# M707A.net
KiCad netlist of a schematic drawn in EAGLE
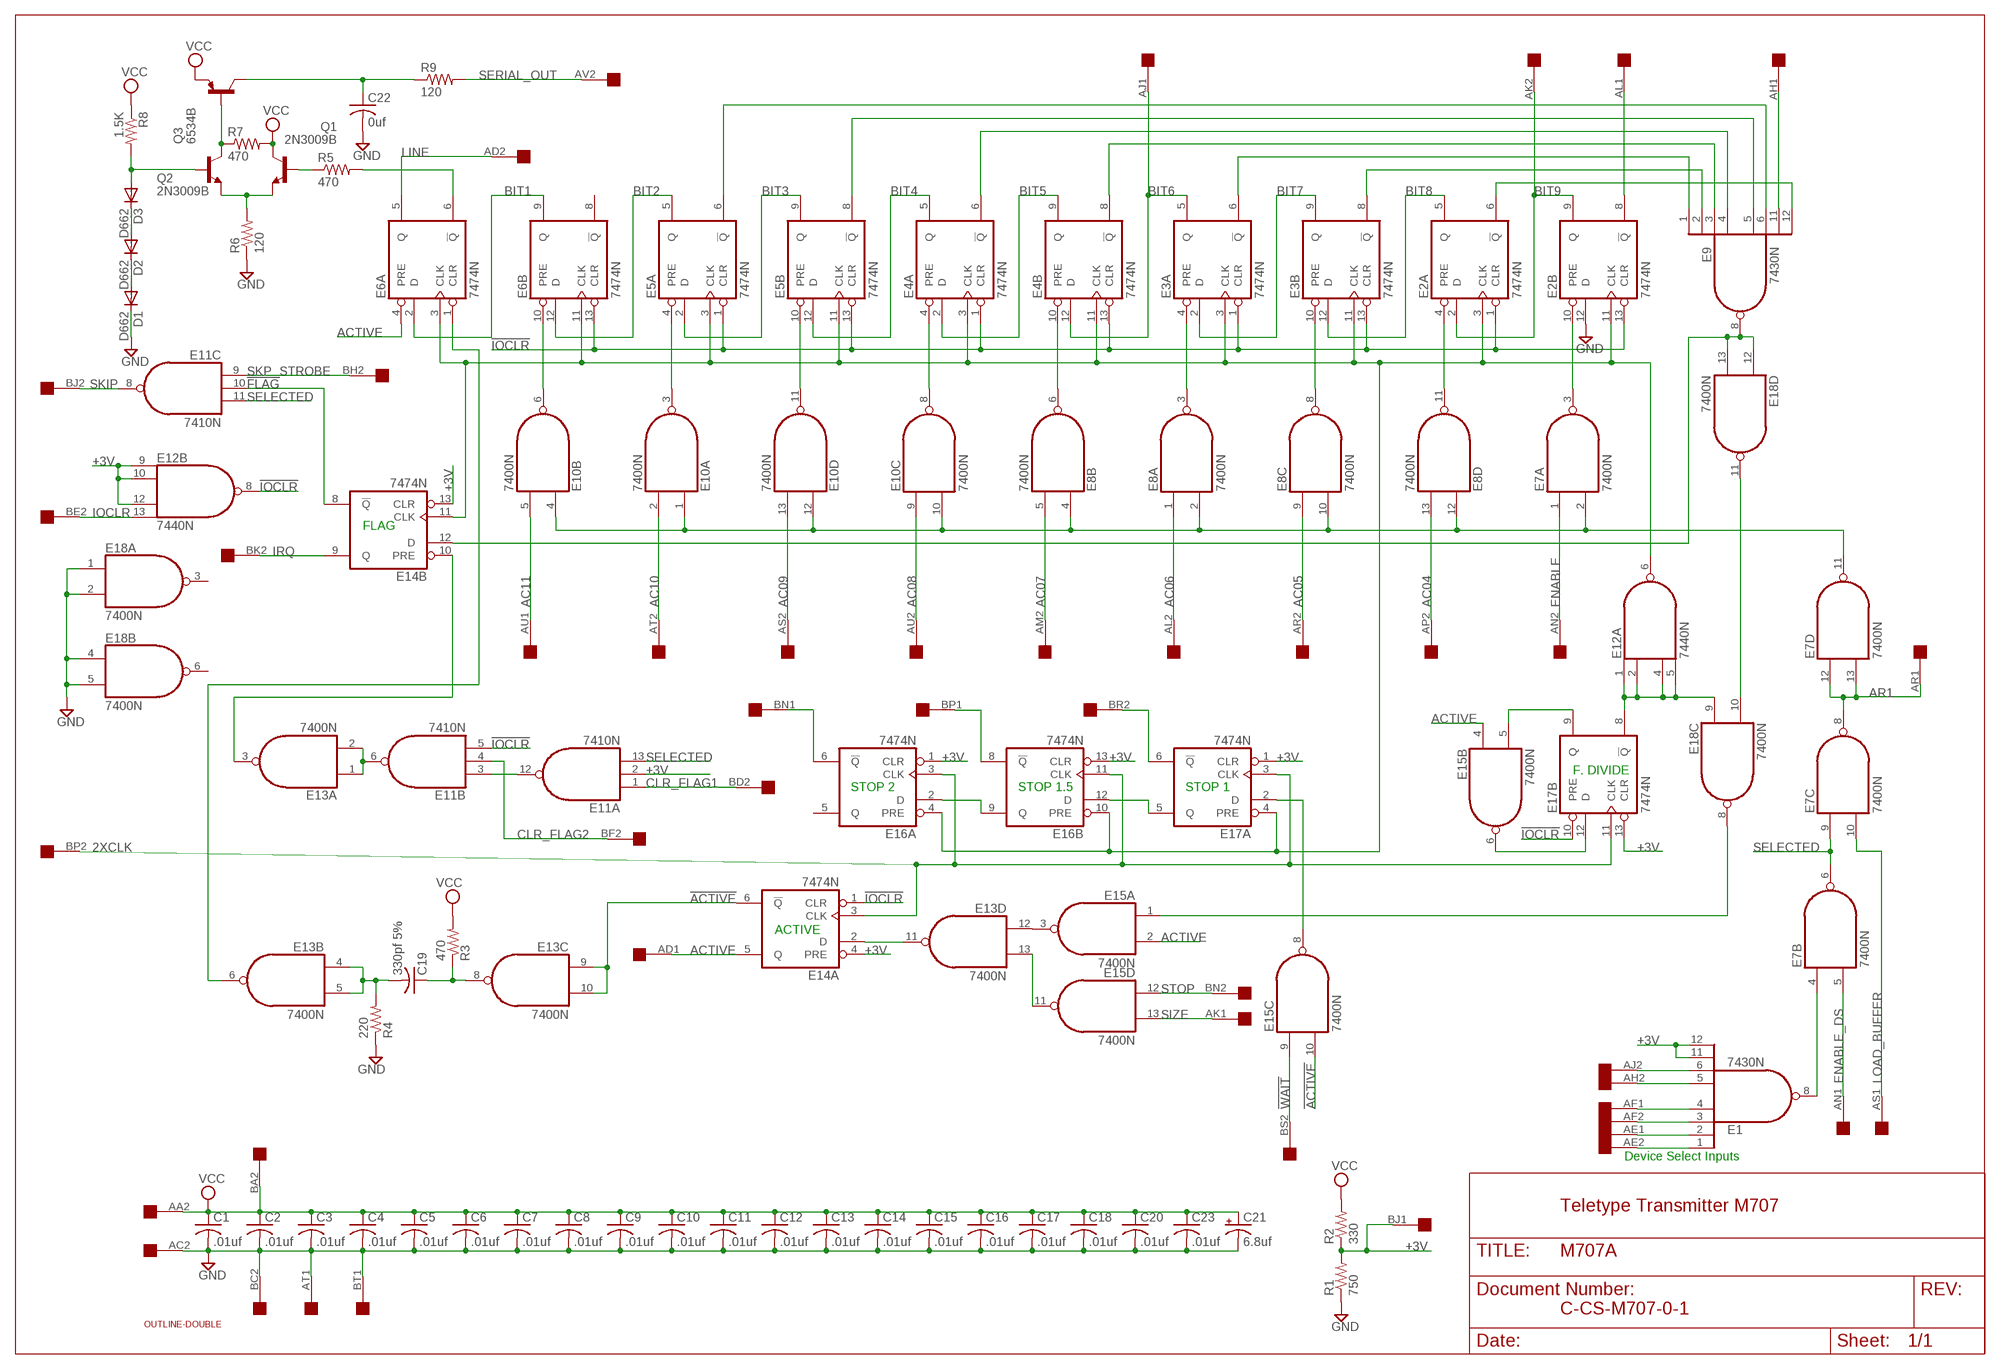
[diagram p0: schematic, sheet 1]

(export (version "E")
  (design (tool "Eeschema 10.0.6"))
  (components
    (comp (ref "C1")
      (value ".01uf")
      (footprint "eagle-import:C075-032X103")
      (libsource (lib "eagle-import") (part "C-US075-032X103"))
    )
    (comp (ref "C2")
      (value ".01uf")
      (footprint "eagle-import:C075-032X103")
      (libsource (lib "eagle-import") (part "C-US075-032X103"))
    )
    (comp (ref "C3")
      (value ".01uf")
      (footprint "eagle-import:C075-032X103")
      (libsource (lib "eagle-import") (part "C-US075-032X103"))
    )
    (comp (ref "C4")
      (value ".01uf")
      (footprint "eagle-import:C075-032X103")
      (libsource (lib "eagle-import") (part "C-US075-032X103"))
    )
    (comp (ref "C5")
      (value ".01uf")
      (footprint "eagle-import:C075-032X103")
      (libsource (lib "eagle-import") (part "C-US075-032X103"))
    )
    (comp (ref "C6")
      (value ".01uf")
      (footprint "eagle-import:C075-032X103")
      (libsource (lib "eagle-import") (part "C-US075-032X103"))
    )
    (comp (ref "C7")
      (value ".01uf")
      (footprint "eagle-import:C075-032X103")
      (libsource (lib "eagle-import") (part "C-US075-032X103"))
    )
    (comp (ref "C8")
      (value ".01uf")
      (footprint "eagle-import:C075-032X103")
      (libsource (lib "eagle-import") (part "C-US075-032X103"))
    )
    (comp (ref "C9")
      (value ".01uf")
      (footprint "eagle-import:C075-032X103")
      (libsource (lib "eagle-import") (part "C-US075-032X103"))
    )
    (comp (ref "C10")
      (value ".01uf")
      (footprint "eagle-import:C075-032X103")
      (libsource (lib "eagle-import") (part "C-US075-032X103"))
    )
    (comp (ref "C11")
      (value ".01uf")
      (footprint "eagle-import:C075-032X103")
      (libsource (lib "eagle-import") (part "C-US075-032X103"))
    )
    (comp (ref "C12")
      (value ".01uf")
      (footprint "eagle-import:C075-032X103")
      (libsource (lib "eagle-import") (part "C-US075-032X103"))
    )
    (comp (ref "C13")
      (value ".01uf")
      (footprint "eagle-import:C075-032X103")
      (libsource (lib "eagle-import") (part "C-US075-032X103"))
    )
    (comp (ref "C14")
      (value ".01uf")
      (footprint "eagle-import:C075-032X103")
      (libsource (lib "eagle-import") (part "C-US075-032X103"))
    )
    (comp (ref "C15")
      (value ".01uf")
      (footprint "eagle-import:C075-032X103")
      (libsource (lib "eagle-import") (part "C-US075-032X103"))
    )
    (comp (ref "C16")
      (value ".01uf")
      (footprint "eagle-import:C075-032X103")
      (libsource (lib "eagle-import") (part "C-US075-032X103"))
    )
    (comp (ref "C17")
      (value ".01uf")
      (footprint "eagle-import:C075-032X103")
      (libsource (lib "eagle-import") (part "C-US075-032X103"))
    )
    (comp (ref "C18")
      (value ".01uf")
      (footprint "eagle-import:C075-032X103")
      (libsource (lib "eagle-import") (part "C-US075-032X103"))
    )
    (comp (ref "C19")
      (value "330pf 5%")
      (footprint "eagle-import:C150-054X183")
      (libsource (lib "eagle-import") (part "C-US150-054X183"))
    )
    (comp (ref "C20")
      (value ".01uf")
      (footprint "eagle-import:C075-032X103")
      (libsource (lib "eagle-import") (part "C-US075-032X103"))
    )
    (comp (ref "C21")
      (value "6.8uf")
      (footprint "eagle-import:E15-5")
      (libsource (lib "eagle-import") (part "CPOL-USE15-5AXIAL"))
    )
    (comp (ref "C22")
      (value "0uf")
      (footprint "eagle-import:C075-032X103")
      (libsource (lib "eagle-import") (part "C-US075-032X103"))
    )
    (comp (ref "C23")
      (value ".01uf")
      (footprint "eagle-import:C075-032X103")
      (libsource (lib "eagle-import") (part "C-US075-032X103"))
    )
    (comp (ref "D1")
      (value "D662")
      (footprint "eagle-import:SOD61B")
      (libsource (lib "eagle-import") (part "BY609"))
    )
    (comp (ref "D2")
      (value "D662")
      (footprint "eagle-import:SOD61B")
      (libsource (lib "eagle-import") (part "BY609"))
    )
    (comp (ref "D3")
      (value "D662")
      (footprint "eagle-import:SOD61B")
      (libsource (lib "eagle-import") (part "BY609"))
    )
    (comp (ref "E1")
      (value "7430N")
      (footprint "eagle-import:DIL14")
      (libsource (lib "eagle-import") (part "7430N"))
    )
    (comp (ref "E2")
      (value "7474N")
      (footprint "eagle-import:DIL14")
      (libsource (lib "eagle-import") (part "7474NS"))
    )
    (comp (ref "E3")
      (value "7474N")
      (footprint "eagle-import:DIL14")
      (libsource (lib "eagle-import") (part "7474NS"))
    )
    (comp (ref "E4")
      (value "7474N")
      (footprint "eagle-import:DIL14")
      (libsource (lib "eagle-import") (part "7474NS"))
    )
    (comp (ref "E5")
      (value "7474N")
      (footprint "eagle-import:DIL14")
      (libsource (lib "eagle-import") (part "7474NS"))
    )
    (comp (ref "E6")
      (value "7474N")
      (footprint "eagle-import:DIL14")
      (libsource (lib "eagle-import") (part "7474NS"))
    )
    (comp (ref "E7")
      (value "7400N")
      (footprint "eagle-import:DIL14")
      (libsource (lib "eagle-import") (part "7400N"))
    )
    (comp (ref "E8")
      (value "7400N")
      (footprint "eagle-import:DIL14")
      (libsource (lib "eagle-import") (part "7400N"))
    )
    (comp (ref "E9")
      (value "7430N")
      (footprint "eagle-import:DIL14")
      (libsource (lib "eagle-import") (part "7430N"))
    )
    (comp (ref "E10")
      (value "7400N")
      (footprint "eagle-import:DIL14")
      (libsource (lib "eagle-import") (part "7400N"))
    )
    (comp (ref "E11")
      (value "7410N")
      (footprint "eagle-import:DIL14")
      (libsource (lib "eagle-import") (part "7410N"))
    )
    (comp (ref "E12")
      (value "7440N")
      (footprint "eagle-import:DIL14")
      (libsource (lib "eagle-import") (part "7420NS"))
    )
    (comp (ref "E13")
      (value "7400N")
      (footprint "eagle-import:DIL14")
      (libsource (lib "eagle-import") (part "7400N"))
    )
    (comp (ref "E14")
      (value "7474N")
      (footprint "eagle-import:DIL14")
      (libsource (lib "eagle-import") (part "7474NS"))
    )
    (comp (ref "E15")
      (value "7400N")
      (footprint "eagle-import:DIL14")
      (libsource (lib "eagle-import") (part "7400N"))
    )
    (comp (ref "E16")
      (value "7474N")
      (footprint "eagle-import:DIL14")
      (libsource (lib "eagle-import") (part "7474NS"))
    )
    (comp (ref "E17")
      (value "7474N")
      (footprint "eagle-import:DIL14")
      (libsource (lib "eagle-import") (part "7474NS"))
    )
    (comp (ref "E18")
      (value "7400N")
      (footprint "eagle-import:DIL14")
      (libsource (lib "eagle-import") (part "7400N"))
    )
    (comp (ref "Q1")
      (value "2N3009B")
      (footprint "eagle-import:TO92-CBE")
      (libsource (lib "eagle-import") (part "-NPN-TO92-CBE2N4124"))
    )
    (comp (ref "Q2")
      (value "2N3009B")
      (footprint "eagle-import:TO92-CBE")
      (libsource (lib "eagle-import") (part "-NPN-TO92-CBE2N4124"))
    )
    (comp (ref "Q3")
      (value "6534B")
      (footprint "eagle-import:TO92-CBE")
      (libsource (lib "eagle-import") (part "-PNP-TO92-CBE2N4126"))
    )
    (comp (ref "R1")
      (value "750")
      (footprint "eagle-import:0207_15")
      (libsource (lib "eagle-import") (part "R-US_0207/15"))
    )
    (comp (ref "R2")
      (value "330")
      (footprint "eagle-import:0207_15")
      (libsource (lib "eagle-import") (part "R-US_0207/15"))
    )
    (comp (ref "R3")
      (value "470")
      (footprint "eagle-import:0207_10")
      (libsource (lib "eagle-import") (part "R-US_0207/10"))
    )
    (comp (ref "R4")
      (value "220")
      (footprint "eagle-import:0207_10")
      (libsource (lib "eagle-import") (part "R-US_0207/10"))
    )
    (comp (ref "R5")
      (value "470")
      (footprint "eagle-import:0207_10")
      (libsource (lib "eagle-import") (part "R-US_0207/10"))
    )
    (comp (ref "R6")
      (value "120")
      (footprint "eagle-import:0207_15")
      (libsource (lib "eagle-import") (part "R-US_0207/15"))
    )
    (comp (ref "R7")
      (value "470")
      (footprint "eagle-import:0207_10")
      (libsource (lib "eagle-import") (part "R-US_0207/10"))
    )
    (comp (ref "R8")
      (value "1.5K")
      (footprint "eagle-import:0207_15")
      (libsource (lib "eagle-import") (part "R-US_0207/15"))
    )
    (comp (ref "R9")
      (value "120")
      (footprint "eagle-import:0207_10")
      (libsource (lib "eagle-import") (part "R-US_0207/10"))
    )
    (comp (ref "U$1")
      (value "OUTLINE-DOUBLE")
      (footprint "eagle-import:DOUBLE")
      (libsource (lib "eagle-import") (part "OUTLINE-DOUBLE"))
    )
    (comp (ref "U$2")
      (value "DOUBLE")
      (footprint "eagle-import:EDGE-CON4")
      (libsource (lib "eagle-import") (part "DOUBLE"))
    )
  )
  (nets
    (net (code "1") (name "/+3V") (class "Default")
      (node (ref "E1") (pin "11") (pinfunction "I6_11") (pintype "input"))
      (node (ref "E1") (pin "12") (pinfunction "I7_12") (pintype "input"))
      (node (ref "E11") (pin "2") (pinfunction "I1_2") (pintype "input"))
      (node (ref "E12") (pin "10") (pinfunction "I1_10") (pintype "input"))
      (node (ref "E12") (pin "12") (pinfunction "I2_12") (pintype "input"))
      (node (ref "E12") (pin "9") (pinfunction "I0_9") (pintype "input"))
      (node (ref "E14") (pin "13") (pinfunction "CLR_13") (pintype "input"))
      (node (ref "E14") (pin "4") (pinfunction "PRE_4") (pintype "input"))
      (node (ref "E16") (pin "1") (pinfunction "CLR_1") (pintype "input"))
      (node (ref "E16") (pin "13") (pinfunction "CLR_13") (pintype "input"))
      (node (ref "E17") (pin "1") (pinfunction "CLR_1") (pintype "input"))
      (node (ref "E17") (pin "13") (pinfunction "CLR_13") (pintype "input"))
      (node (ref "R1") (pin "2") (pinfunction "2_2") (pintype "passive"))
      (node (ref "R2") (pin "1") (pinfunction "1_1") (pintype "passive"))
      (node (ref "U$2") (pin "BJ1") (pinfunction "1_BJ1") (pintype "bidirectional"))
    )
    (net (code "2") (name "/2XCLK") (class "Default")
      (node (ref "E14") (pin "3") (pinfunction "CLK_3") (pintype "input"))
      (node (ref "E16") (pin "11") (pinfunction "CLK_11") (pintype "input"))
      (node (ref "E16") (pin "3") (pinfunction "CLK_3") (pintype "input"))
      (node (ref "E17") (pin "11") (pinfunction "CLK_11") (pintype "input"))
      (node (ref "E17") (pin "3") (pinfunction "CLK_3") (pintype "input"))
      (node (ref "U$2") (pin "BP2") (pinfunction "1_BP2") (pintype "bidirectional"))
    )
    (net (code "3") (name "/AC04") (class "Default")
      (node (ref "E8") (pin "13") (pinfunction "I1_13") (pintype "input"))
      (node (ref "U$2") (pin "AP2") (pinfunction "1_AP2") (pintype "bidirectional"))
    )
    (net (code "4") (name "/AC05") (class "Default")
      (node (ref "E8") (pin "9") (pinfunction "I0_9") (pintype "input"))
      (node (ref "U$2") (pin "AR2") (pinfunction "1_AR2") (pintype "bidirectional"))
    )
    (net (code "5") (name "/AC06") (class "Default")
      (node (ref "E8") (pin "1") (pinfunction "I0_1") (pintype "input"))
      (node (ref "U$2") (pin "AL2") (pinfunction "1_AL2") (pintype "bidirectional"))
    )
    (net (code "6") (name "/AC07") (class "Default")
      (node (ref "E8") (pin "5") (pinfunction "I1_5") (pintype "input"))
      (node (ref "U$2") (pin "AM2") (pinfunction "1_AM2") (pintype "bidirectional"))
    )
    (net (code "7") (name "/AC08") (class "Default")
      (node (ref "E10") (pin "9") (pinfunction "I0_9") (pintype "input"))
      (node (ref "U$2") (pin "AU2") (pinfunction "1_AU2") (pintype "bidirectional"))
    )
    (net (code "8") (name "/AC09") (class "Default")
      (node (ref "E10") (pin "13") (pinfunction "I1_13") (pintype "input"))
      (node (ref "U$2") (pin "AS2") (pinfunction "1_AS2") (pintype "bidirectional"))
    )
    (net (code "9") (name "/AC10") (class "Default")
      (node (ref "E10") (pin "2") (pinfunction "I1_2") (pintype "input"))
      (node (ref "U$2") (pin "AT2") (pinfunction "1_AT2") (pintype "bidirectional"))
    )
    (net (code "10") (name "/AC11") (class "Default")
      (node (ref "E10") (pin "5") (pinfunction "I1_5") (pintype "input"))
      (node (ref "U$2") (pin "AU1") (pinfunction "1_AU1") (pintype "bidirectional"))
    )
    (net (code "11") (name "/ACTIVE") (class "Default")
      (node (ref "E14") (pin "5") (pinfunction "Q_5") (pintype "output"))
      (node (ref "E15") (pin "2") (pinfunction "I1_2") (pintype "input"))
      (node (ref "E15") (pin "4") (pinfunction "I0_4") (pintype "input"))
      (node (ref "E6") (pin "4") (pinfunction "PRE_4") (pintype "input"))
      (node (ref "U$2") (pin "AD1") (pinfunction "1_AD1") (pintype "bidirectional"))
    )
    (net (code "12") (name "/AR1") (class "Default")
      (node (ref "E7") (pin "12") (pinfunction "I0_12") (pintype "input"))
      (node (ref "E7") (pin "13") (pinfunction "I1_13") (pintype "input"))
      (node (ref "E7") (pin "8") (pinfunction "O_8") (pintype "output"))
      (node (ref "U$2") (pin "AR1") (pinfunction "1_AR1") (pintype "bidirectional"))
    )
    (net (code "13") (name "/BIT1") (class "Default")
      (node (ref "E6") (pin "2") (pinfunction "D_2") (pintype "input"))
      (node (ref "E6") (pin "9") (pinfunction "Q_9") (pintype "output"))
    )
    (net (code "14") (name "/BIT2") (class "Default")
      (node (ref "E5") (pin "5") (pinfunction "Q_5") (pintype "output"))
      (node (ref "E6") (pin "12") (pinfunction "D_12") (pintype "input"))
    )
    (net (code "15") (name "/BIT3") (class "Default")
      (node (ref "E5") (pin "2") (pinfunction "D_2") (pintype "input"))
      (node (ref "E5") (pin "9") (pinfunction "Q_9") (pintype "output"))
    )
    (net (code "16") (name "/BIT4") (class "Default")
      (node (ref "E4") (pin "5") (pinfunction "Q_5") (pintype "output"))
      (node (ref "E5") (pin "12") (pinfunction "D_12") (pintype "input"))
    )
    (net (code "17") (name "/BIT5") (class "Default")
      (node (ref "E4") (pin "2") (pinfunction "D_2") (pintype "input"))
      (node (ref "E4") (pin "9") (pinfunction "Q_9") (pintype "output"))
    )
    (net (code "18") (name "/BIT6") (class "Default")
      (node (ref "E3") (pin "5") (pinfunction "Q_5") (pintype "output"))
      (node (ref "E4") (pin "12") (pinfunction "D_12") (pintype "input"))
      (node (ref "U$2") (pin "AJ1") (pinfunction "1_AJ1") (pintype "bidirectional"))
    )
    (net (code "19") (name "/BIT7") (class "Default")
      (node (ref "E3") (pin "2") (pinfunction "D_2") (pintype "input"))
      (node (ref "E3") (pin "9") (pinfunction "Q_9") (pintype "output"))
    )
    (net (code "20") (name "/BIT8") (class "Default")
      (node (ref "E2") (pin "5") (pinfunction "Q_5") (pintype "output"))
      (node (ref "E3") (pin "12") (pinfunction "D_12") (pintype "input"))
    )
    (net (code "21") (name "/BIT9") (class "Default")
      (node (ref "E2") (pin "2") (pinfunction "D_2") (pintype "input"))
      (node (ref "E2") (pin "9") (pinfunction "Q_9") (pintype "output"))
      (node (ref "U$2") (pin "AK2") (pinfunction "1_AK2") (pintype "bidirectional"))
    )
    (net (code "22") (name "/CLR_FLAG1") (class "Default")
      (node (ref "E11") (pin "1") (pinfunction "I0_1") (pintype "input"))
      (node (ref "U$2") (pin "BD2") (pinfunction "1_BD2") (pintype "bidirectional"))
    )
    (net (code "23") (name "/CLR_FLAG2") (class "Default")
      (node (ref "E11") (pin "4") (pinfunction "I1_4") (pintype "input"))
      (node (ref "U$2") (pin "BF2") (pinfunction "1_BF2") (pintype "bidirectional"))
    )
    (net (code "24") (name "/ENABLE") (class "Default")
      (node (ref "E7") (pin "1") (pinfunction "I0_1") (pintype "input"))
      (node (ref "U$2") (pin "AN2") (pinfunction "1_AN2") (pintype "bidirectional"))
    )
    (net (code "25") (name "/ENABLE_DS") (class "Default")
      (node (ref "E7") (pin "5") (pinfunction "I1_5") (pintype "input"))
      (node (ref "U$2") (pin "AN1") (pinfunction "1_AN1") (pintype "bidirectional"))
    )
    (net (code "26") (name "/IOCLR") (class "Default")
      (node (ref "E12") (pin "13") (pinfunction "I3_13") (pintype "input"))
      (node (ref "U$2") (pin "BE2") (pinfunction "1_BE2") (pintype "bidirectional"))
    )
    (net (code "27") (name "/IRQ") (class "Default")
      (node (ref "E14") (pin "9") (pinfunction "Q_9") (pintype "output"))
      (node (ref "U$2") (pin "BK2") (pinfunction "1_BK2") (pintype "bidirectional"))
    )
    (net (code "28") (name "/LINE") (class "Default")
      (node (ref "E6") (pin "5") (pinfunction "Q_5") (pintype "output"))
      (node (ref "U$2") (pin "AD2") (pinfunction "1_AD2") (pintype "bidirectional"))
    )
    (net (code "29") (name "/LOAD_BUFFER") (class "Default")
      (node (ref "E7") (pin "10") (pinfunction "I1_10") (pintype "input"))
      (node (ref "U$2") (pin "AS1") (pinfunction "1_AS1") (pintype "bidirectional"))
    )
    (net (code "30") (name "/SELECTED") (class "Default")
      (node (ref "E11") (pin "11") (pinfunction "I2_11") (pintype "input"))
      (node (ref "E11") (pin "13") (pinfunction "I2_13") (pintype "input"))
      (node (ref "E7") (pin "6") (pinfunction "O_6") (pintype "output"))
      (node (ref "E7") (pin "9") (pinfunction "I0_9") (pintype "input"))
    )
    (net (code "31") (name "/SERIAL_OUT") (class "Default")
      (node (ref "R9") (pin "2") (pinfunction "2_2") (pintype "passive"))
      (node (ref "U$2") (pin "AV2") (pinfunction "1_AV2") (pintype "bidirectional"))
    )
    (net (code "32") (name "/SIZE") (class "Default")
      (node (ref "E15") (pin "13") (pinfunction "I1_13") (pintype "input"))
      (node (ref "U$2") (pin "AK1") (pinfunction "1_AK1") (pintype "bidirectional"))
    )
    (net (code "33") (name "/SKIP") (class "Default")
      (node (ref "E11") (pin "8") (pinfunction "O_8") (pintype "output"))
      (node (ref "U$2") (pin "BJ2") (pinfunction "1_BJ2") (pintype "bidirectional"))
    )
    (net (code "34") (name "/SKP_STROBE") (class "Default")
      (node (ref "E11") (pin "9") (pinfunction "I0_9") (pintype "input"))
      (node (ref "U$2") (pin "BH2") (pinfunction "1_BH2") (pintype "bidirectional"))
    )
    (net (code "35") (name "/STOP") (class "Default")
      (node (ref "E15") (pin "12") (pinfunction "I0_12") (pintype "input"))
      (node (ref "U$2") (pin "BN2") (pinfunction "1_BN2") (pintype "bidirectional"))
    )
    (net (code "36") (name "/~{ACTIVE}") (class "Default")
      (node (ref "E13") (pin "10") (pinfunction "I1_10") (pintype "input"))
      (node (ref "E13") (pin "9") (pinfunction "I0_9") (pintype "input"))
      (node (ref "E14") (pin "6") (pinfunction "~{Q}_6") (pintype "output"))
      (node (ref "E15") (pin "10") (pinfunction "I1_10") (pintype "input"))
    )
    (net (code "37") (name "/~{FLAG}") (class "Default")
      (node (ref "E11") (pin "10") (pinfunction "I1_10") (pintype "input"))
      (node (ref "E14") (pin "8") (pinfunction "~{Q}_8") (pintype "output"))
    )
    (net (code "38") (name "/~{IOCLR}") (class "Default")
      (node (ref "E11") (pin "5") (pinfunction "I2_5") (pintype "input"))
      (node (ref "E12") (pin "8") (pinfunction "O_8") (pintype "output"))
      (node (ref "E14") (pin "1") (pinfunction "CLR_1") (pintype "input"))
      (node (ref "E17") (pin "10") (pinfunction "PRE_10") (pintype "input"))
      (node (ref "E2") (pin "1") (pinfunction "CLR_1") (pintype "input"))
      (node (ref "E2") (pin "13") (pinfunction "CLR_13") (pintype "input"))
      (node (ref "E3") (pin "1") (pinfunction "CLR_1") (pintype "input"))
      (node (ref "E3") (pin "13") (pinfunction "CLR_13") (pintype "input"))
      (node (ref "E4") (pin "1") (pinfunction "CLR_1") (pintype "input"))
      (node (ref "E4") (pin "13") (pinfunction "CLR_13") (pintype "input"))
      (node (ref "E5") (pin "1") (pinfunction "CLR_1") (pintype "input"))
      (node (ref "E5") (pin "13") (pinfunction "CLR_13") (pintype "input"))
      (node (ref "E6") (pin "13") (pinfunction "CLR_13") (pintype "input"))
    )
    (net (code "39") (name "/~{WAIT}") (class "Default")
      (node (ref "E15") (pin "9") (pinfunction "I0_9") (pintype "input"))
      (node (ref "U$2") (pin "BS2") (pinfunction "1_BS2") (pintype "bidirectional"))
    )
    (net (code "40") (name "GND") (class "Default")
      (node (ref "C1") (pin "2") (pinfunction "2_2") (pintype "passive"))
      (node (ref "C10") (pin "2") (pinfunction "2_2") (pintype "passive"))
      (node (ref "C11") (pin "2") (pinfunction "2_2") (pintype "passive"))
      (node (ref "C12") (pin "2") (pinfunction "2_2") (pintype "passive"))
      (node (ref "C13") (pin "2") (pinfunction "2_2") (pintype "passive"))
      (node (ref "C14") (pin "2") (pinfunction "2_2") (pintype "passive"))
      (node (ref "C15") (pin "2") (pinfunction "2_2") (pintype "passive"))
      (node (ref "C16") (pin "2") (pinfunction "2_2") (pintype "passive"))
      (node (ref "C17") (pin "2") (pinfunction "2_2") (pintype "passive"))
      (node (ref "C18") (pin "2") (pinfunction "2_2") (pintype "passive"))
      (node (ref "C2") (pin "2") (pinfunction "2_2") (pintype "passive"))
      (node (ref "C20") (pin "2") (pinfunction "2_2") (pintype "passive"))
      (node (ref "C21") (pin "-") (pinfunction "-_-") (pintype "passive"))
      (node (ref "C22") (pin "2") (pinfunction "2_2") (pintype "passive"))
      (node (ref "C23") (pin "2") (pinfunction "2_2") (pintype "passive"))
      (node (ref "C3") (pin "2") (pinfunction "2_2") (pintype "passive"))
      (node (ref "C4") (pin "2") (pinfunction "2_2") (pintype "passive"))
      (node (ref "C5") (pin "2") (pinfunction "2_2") (pintype "passive"))
      (node (ref "C6") (pin "2") (pinfunction "2_2") (pintype "passive"))
      (node (ref "C7") (pin "2") (pinfunction "2_2") (pintype "passive"))
      (node (ref "C8") (pin "2") (pinfunction "2_2") (pintype "passive"))
      (node (ref "C9") (pin "2") (pinfunction "2_2") (pintype "passive"))
      (node (ref "D1") (pin "C") (pinfunction "C_C") (pintype "passive"))
      (node (ref "E18") (pin "1") (pinfunction "I0_1") (pintype "input"))
      (node (ref "E18") (pin "2") (pinfunction "I1_2") (pintype "input"))
      (node (ref "E18") (pin "4") (pinfunction "I0_4") (pintype "input"))
      (node (ref "E18") (pin "5") (pinfunction "I1_5") (pintype "input"))
      (node (ref "E2") (pin "12") (pinfunction "D_12") (pintype "input"))
      (node (ref "R1") (pin "1") (pinfunction "1_1") (pintype "passive"))
      (node (ref "R4") (pin "1") (pinfunction "1_1") (pintype "passive"))
      (node (ref "R6") (pin "1") (pinfunction "1_1") (pintype "passive"))
      (node (ref "U$2") (pin "AC2") (pinfunction "1_AC2") (pintype "bidirectional"))
      (node (ref "U$2") (pin "AT1") (pinfunction "1_AT1") (pintype "bidirectional"))
      (node (ref "U$2") (pin "BC2") (pinfunction "1_BC2") (pintype "bidirectional"))
      (node (ref "U$2") (pin "BT1") (pinfunction "1_BT1") (pintype "bidirectional"))
    )
    (net (code "41") (name "Net-(C22-Pad1)") (class "Default")
      (node (ref "C22") (pin "1") (pinfunction "1_1") (pintype "passive"))
      (node (ref "Q3") (pin "C") (pinfunction "C_C") (pintype "passive"))
      (node (ref "R9") (pin "1") (pinfunction "1_1") (pintype "passive"))
    )
    (net (code "42") (name "Net-(D1-PadA)") (class "Default")
      (node (ref "D1") (pin "A") (pinfunction "A_A") (pintype "passive"))
      (node (ref "D2") (pin "C") (pinfunction "C_C") (pintype "passive"))
    )
    (net (code "43") (name "Net-(D2-PadA)") (class "Default")
      (node (ref "D2") (pin "A") (pinfunction "A_A") (pintype "passive"))
      (node (ref "D3") (pin "C") (pinfunction "C_C") (pintype "passive"))
    )
    (net (code "44") (name "Net-(D3-PadA)") (class "Default")
      (node (ref "D3") (pin "A") (pinfunction "A_A") (pintype "passive"))
      (node (ref "Q2") (pin "B") (pinfunction "B_B") (pintype "passive"))
      (node (ref "R8") (pin "2") (pinfunction "2_2") (pintype "passive"))
    )
    (net (code "45") (name "Net-(E1A-I0)") (class "Default")
      (node (ref "E1") (pin "1") (pinfunction "I0_1") (pintype "input"))
      (node (ref "U$2") (pin "AE2") (pinfunction "1_AE2") (pintype "bidirectional"))
    )
    (net (code "46") (name "Net-(E1A-I1)") (class "Default")
      (node (ref "E1") (pin "2") (pinfunction "I1_2") (pintype "input"))
      (node (ref "U$2") (pin "AE1") (pinfunction "1_AE1") (pintype "bidirectional"))
    )
    (net (code "47") (name "Net-(E1A-I2)") (class "Default")
      (node (ref "E1") (pin "3") (pinfunction "I2_3") (pintype "input"))
      (node (ref "U$2") (pin "AF2") (pinfunction "1_AF2") (pintype "bidirectional"))
    )
    (net (code "48") (name "Net-(E1A-I3)") (class "Default")
      (node (ref "E1") (pin "4") (pinfunction "I3_4") (pintype "input"))
      (node (ref "U$2") (pin "AF1") (pinfunction "1_AF1") (pintype "bidirectional"))
    )
    (net (code "49") (name "Net-(E1A-I4)") (class "Default")
      (node (ref "E1") (pin "5") (pinfunction "I4_5") (pintype "input"))
      (node (ref "U$2") (pin "AH2") (pinfunction "1_AH2") (pintype "bidirectional"))
    )
    (net (code "50") (name "Net-(E1A-I5)") (class "Default")
      (node (ref "E1") (pin "6") (pinfunction "I5_6") (pintype "input"))
      (node (ref "U$2") (pin "AJ2") (pinfunction "1_AJ2") (pintype "bidirectional"))
    )
    (net (code "51") (name "Net-(E1A-O)") (class "Default")
      (node (ref "E1") (pin "8") (pinfunction "O_8") (pintype "output"))
      (node (ref "E7") (pin "4") (pinfunction "I0_4") (pintype "input"))
    )
    (net (code "52") (name "Net-(E2A-PRE)") (class "Default")
      (node (ref "E2") (pin "4") (pinfunction "PRE_4") (pintype "input"))
      (node (ref "E8") (pin "11") (pinfunction "O_11") (pintype "output"))
    )
    (net (code "53") (name "Net-(E2A-~{Q})") (class "Default")
      (node (ref "E2") (pin "6") (pinfunction "~{Q}_6") (pintype "output"))
      (node (ref "E9") (pin "12") (pinfunction "I7_12") (pintype "input"))
    )
    (net (code "54") (name "Net-(E2B-PRE)") (class "Default")
      (node (ref "E2") (pin "10") (pinfunction "PRE_10") (pintype "input"))
      (node (ref "E7") (pin "3") (pinfunction "O_3") (pintype "output"))
    )
    (net (code "55") (name "Net-(E2B-~{Q})") (class "Default")
      (node (ref "E2") (pin "8") (pinfunction "~{Q}_8") (pintype "output"))
      (node (ref "U$2") (pin "AL1") (pinfunction "1_AL1") (pintype "bidirectional"))
    )
    (net (code "56") (name "Net-(E3A-PRE)") (class "Default")
      (node (ref "E3") (pin "4") (pinfunction "PRE_4") (pintype "input"))
      (node (ref "E8") (pin "3") (pinfunction "O_3") (pintype "output"))
    )
    (net (code "57") (name "Net-(E3A-~{Q})") (class "Default")
      (node (ref "E3") (pin "6") (pinfunction "~{Q}_6") (pintype "output"))
      (node (ref "E9") (pin "1") (pinfunction "I0_1") (pintype "input"))
    )
    (net (code "58") (name "Net-(E3B-PRE)") (class "Default")
      (node (ref "E3") (pin "10") (pinfunction "PRE_10") (pintype "input"))
      (node (ref "E8") (pin "8") (pinfunction "O_8") (pintype "output"))
    )
    (net (code "59") (name "Net-(E3B-~{Q})") (class "Default")
      (node (ref "E3") (pin "8") (pinfunction "~{Q}_8") (pintype "output"))
      (node (ref "E9") (pin "2") (pinfunction "I1_2") (pintype "input"))
    )
    (net (code "60") (name "Net-(E4A-~{Q})") (class "Default")
      (node (ref "E4") (pin "6") (pinfunction "~{Q}_6") (pintype "output"))
      (node (ref "E9") (pin "4") (pinfunction "I3_4") (pintype "input"))
    )
    (net (code "61") (name "Net-(E4B-PRE)") (class "Default")
      (node (ref "E4") (pin "10") (pinfunction "PRE_10") (pintype "input"))
      (node (ref "E8") (pin "6") (pinfunction "O_6") (pintype "output"))
    )
    (net (code "62") (name "Net-(E4B-~{Q})") (class "Default")
      (node (ref "E4") (pin "8") (pinfunction "~{Q}_8") (pintype "output"))
      (node (ref "E9") (pin "3") (pinfunction "I2_3") (pintype "input"))
    )
    (net (code "63") (name "Net-(E5A-~{Q})") (class "Default")
      (node (ref "E5") (pin "6") (pinfunction "~{Q}_6") (pintype "output"))
      (node (ref "E9") (pin "6") (pinfunction "I5_6") (pintype "input"))
    )
    (net (code "64") (name "Net-(E5B-~{Q})") (class "Default")
      (node (ref "E5") (pin "8") (pinfunction "~{Q}_8") (pintype "output"))
      (node (ref "E9") (pin "5") (pinfunction "I4_5") (pintype "input"))
    )
    (net (code "65") (name "Net-(E6A-~{Q})") (class "Default")
      (node (ref "E6") (pin "6") (pinfunction "~{Q}_6") (pintype "output"))
      (node (ref "R5") (pin "2") (pinfunction "2_2") (pintype "passive"))
    )
    (net (code "66") (name "Net-(E9A-I6)") (class "Default")
      (node (ref "E9") (pin "11") (pinfunction "I6_11") (pintype "input"))
      (node (ref "U$2") (pin "AH1") (pinfunction "1_AH1") (pintype "bidirectional"))
    )
    (net (code "67") (name "Net-(E10A-I0)") (class "Default")
      (node (ref "E10") (pin "1") (pinfunction "I0_1") (pintype "input"))
      (node (ref "E10") (pin "10") (pinfunction "I1_10") (pintype "input"))
      (node (ref "E10") (pin "12") (pinfunction "I0_12") (pintype "input"))
      (node (ref "E10") (pin "4") (pinfunction "I0_4") (pintype "input"))
      (node (ref "E7") (pin "11") (pinfunction "O_11") (pintype "output"))
      (node (ref "E7") (pin "2") (pinfunction "I1_2") (pintype "input"))
      (node (ref "E8") (pin "10") (pinfunction "I1_10") (pintype "input"))
      (node (ref "E8") (pin "12") (pinfunction "I0_12") (pintype "input"))
      (node (ref "E8") (pin "2") (pinfunction "I1_2") (pintype "input"))
      (node (ref "E8") (pin "4") (pinfunction "I0_4") (pintype "input"))
    )
    (net (code "68") (name "Net-(E10A-O)") (class "Default")
      (node (ref "E10") (pin "3") (pinfunction "O_3") (pintype "output"))
      (node (ref "E5") (pin "4") (pinfunction "PRE_4") (pintype "input"))
    )
    (net (code "69") (name "Net-(E10B-O)") (class "Default")
      (node (ref "E10") (pin "6") (pinfunction "O_6") (pintype "output"))
      (node (ref "E6") (pin "10") (pinfunction "PRE_10") (pintype "input"))
    )
    (net (code "70") (name "Net-(E10C-O)") (class "Default")
      (node (ref "E10") (pin "8") (pinfunction "O_8") (pintype "output"))
      (node (ref "E4") (pin "4") (pinfunction "PRE_4") (pintype "input"))
    )
    (net (code "71") (name "Net-(E10D-O)") (class "Default")
      (node (ref "E10") (pin "11") (pinfunction "O_11") (pintype "output"))
      (node (ref "E5") (pin "10") (pinfunction "PRE_10") (pintype "input"))
    )
    (net (code "72") (name "Net-(E11A-O)") (class "Default")
      (node (ref "E11") (pin "12") (pinfunction "O_12") (pintype "output"))
      (node (ref "E11") (pin "3") (pinfunction "I0_3") (pintype "input"))
    )
    (net (code "73") (name "Net-(E11B-O)") (class "Default")
      (node (ref "E11") (pin "6") (pinfunction "O_6") (pintype "output"))
      (node (ref "E13") (pin "1") (pinfunction "I0_1") (pintype "input"))
      (node (ref "E13") (pin "2") (pinfunction "I1_2") (pintype "input"))
    )
    (net (code "74") (name "Net-(E12A-I0)") (class "Default")
      (node (ref "E12") (pin "1") (pinfunction "I0_1") (pintype "input"))
      (node (ref "E12") (pin "2") (pinfunction "I1_2") (pintype "input"))
      (node (ref "E12") (pin "4") (pinfunction "I2_4") (pintype "input"))
      (node (ref "E12") (pin "5") (pinfunction "I3_5") (pintype "input"))
      (node (ref "E17") (pin "8") (pinfunction "~{Q}_8") (pintype "output"))
      (node (ref "E18") (pin "9") (pinfunction "I0_9") (pintype "input"))
    )
    (net (code "75") (name "Net-(E12A-O)") (class "Default")
      (node (ref "E12") (pin "6") (pinfunction "O_6") (pintype "output"))
      (node (ref "E14") (pin "11") (pinfunction "CLK_11") (pintype "input"))
      (node (ref "E16") (pin "10") (pinfunction "PRE_10") (pintype "input"))
      (node (ref "E16") (pin "4") (pinfunction "PRE_4") (pintype "input"))
      (node (ref "E17") (pin "4") (pinfunction "PRE_4") (pintype "input"))
      (node (ref "E2") (pin "11") (pinfunction "CLK_11") (pintype "input"))
      (node (ref "E2") (pin "3") (pinfunction "CLK_3") (pintype "input"))
      (node (ref "E3") (pin "11") (pinfunction "CLK_11") (pintype "input"))
      (node (ref "E3") (pin "3") (pinfunction "CLK_3") (pintype "input"))
      (node (ref "E4") (pin "11") (pinfunction "CLK_11") (pintype "input"))
      (node (ref "E4") (pin "3") (pinfunction "CLK_3") (pintype "input"))
      (node (ref "E5") (pin "11") (pinfunction "CLK_11") (pintype "input"))
      (node (ref "E5") (pin "3") (pinfunction "CLK_3") (pintype "input"))
      (node (ref "E6") (pin "11") (pinfunction "CLK_11") (pintype "input"))
      (node (ref "E6") (pin "3") (pinfunction "CLK_3") (pintype "input"))
    )
    (net (code "76") (name "Net-(E13A-O)") (class "Default")
      (node (ref "E13") (pin "3") (pinfunction "O_3") (pintype "output"))
      (node (ref "E14") (pin "10") (pinfunction "PRE_10") (pintype "input"))
    )
    (net (code "77") (name "Net-(E13B-I0)") (class "Default")
      (node (ref "C19") (pin "2") (pinfunction "2_2") (pintype "passive"))
      (node (ref "E13") (pin "4") (pinfunction "I0_4") (pintype "input"))
      (node (ref "E13") (pin "5") (pinfunction "I1_5") (pintype "input"))
      (node (ref "R4") (pin "2") (pinfunction "2_2") (pintype "passive"))
    )
    (net (code "78") (name "Net-(E13B-O)") (class "Default")
      (node (ref "E13") (pin "6") (pinfunction "O_6") (pintype "output"))
      (node (ref "E6") (pin "1") (pinfunction "CLR_1") (pintype "input"))
    )
    (net (code "79") (name "Net-(E13C-O)") (class "Default")
      (node (ref "C19") (pin "1") (pinfunction "1_1") (pintype "passive"))
      (node (ref "E13") (pin "8") (pinfunction "O_8") (pintype "output"))
      (node (ref "R3") (pin "1") (pinfunction "1_1") (pintype "passive"))
    )
    (net (code "80") (name "Net-(E13D-I0)") (class "Default")
      (node (ref "E13") (pin "12") (pinfunction "I0_12") (pintype "input"))
      (node (ref "E15") (pin "3") (pinfunction "O_3") (pintype "output"))
    )
    (net (code "81") (name "Net-(E13D-I1)") (class "Default")
      (node (ref "E13") (pin "13") (pinfunction "I1_13") (pintype "input"))
      (node (ref "E15") (pin "11") (pinfunction "O_11") (pintype "output"))
    )
    (net (code "82") (name "Net-(E13D-O)") (class "Default")
      (node (ref "E13") (pin "11") (pinfunction "O_11") (pintype "output"))
      (node (ref "E14") (pin "2") (pinfunction "D_2") (pintype "input"))
    )
    (net (code "83") (name "Net-(E14B-D)") (class "Default")
      (node (ref "E14") (pin "12") (pinfunction "D_12") (pintype "input"))
      (node (ref "E18") (pin "12") (pinfunction "I0_12") (pintype "input"))
      (node (ref "E18") (pin "13") (pinfunction "I1_13") (pintype "input"))
      (node (ref "E9") (pin "8") (pinfunction "O_8") (pintype "output"))
    )
    (net (code "84") (name "Net-(E15A-I0)") (class "Default")
      (node (ref "E15") (pin "1") (pinfunction "I0_1") (pintype "input"))
      (node (ref "E18") (pin "8") (pinfunction "O_8") (pintype "output"))
    )
    (net (code "85") (name "Net-(E15B-I1)") (class "Default")
      (node (ref "E15") (pin "5") (pinfunction "I1_5") (pintype "input"))
      (node (ref "E17") (pin "9") (pinfunction "Q_9") (pintype "output"))
    )
    (net (code "86") (name "Net-(E15B-O)") (class "Default")
      (node (ref "E15") (pin "6") (pinfunction "O_6") (pintype "output"))
      (node (ref "E17") (pin "12") (pinfunction "D_12") (pintype "input"))
    )
    (net (code "87") (name "Net-(E15C-O)") (class "Default")
      (node (ref "E15") (pin "8") (pinfunction "O_8") (pintype "output"))
      (node (ref "E17") (pin "2") (pinfunction "D_2") (pintype "input"))
    )
    (net (code "88") (name "Net-(E16A-D)") (class "Default")
      (node (ref "E16") (pin "2") (pinfunction "D_2") (pintype "input"))
      (node (ref "E16") (pin "9") (pinfunction "Q_9") (pintype "output"))
    )
    (net (code "89") (name "Net-(E16A-~{Q})") (class "Default")
      (node (ref "E16") (pin "6") (pinfunction "~{Q}_6") (pintype "output"))
      (node (ref "U$2") (pin "BN1") (pinfunction "1_BN1") (pintype "bidirectional"))
    )
    (net (code "90") (name "Net-(E16B-D)") (class "Default")
      (node (ref "E16") (pin "12") (pinfunction "D_12") (pintype "input"))
      (node (ref "E17") (pin "5") (pinfunction "Q_5") (pintype "output"))
    )
    (net (code "91") (name "Net-(E16B-~{Q})") (class "Default")
      (node (ref "E16") (pin "8") (pinfunction "~{Q}_8") (pintype "output"))
      (node (ref "U$2") (pin "BP1") (pinfunction "1_BP1") (pintype "bidirectional"))
    )
    (net (code "92") (name "Net-(E17A-~{Q})") (class "Default")
      (node (ref "E17") (pin "6") (pinfunction "~{Q}_6") (pintype "output"))
      (node (ref "U$2") (pin "BR2") (pinfunction "1_BR2") (pintype "bidirectional"))
    )
    (net (code "93") (name "Net-(E18C-I1)") (class "Default")
      (node (ref "E18") (pin "10") (pinfunction "I1_10") (pintype "input"))
      (node (ref "E18") (pin "11") (pinfunction "O_11") (pintype "output"))
    )
    (net (code "94") (name "Net-(Q1-PadB)") (class "Default")
      (node (ref "Q1") (pin "B") (pinfunction "B_B") (pintype "passive"))
      (node (ref "R5") (pin "1") (pinfunction "1_1") (pintype "passive"))
    )
    (net (code "95") (name "Net-(Q1-PadE)") (class "Default")
      (node (ref "Q1") (pin "E") (pinfunction "E_E") (pintype "passive"))
      (node (ref "Q2") (pin "E") (pinfunction "E_E") (pintype "passive"))
      (node (ref "R6") (pin "2") (pinfunction "2_2") (pintype "passive"))
    )
    (net (code "96") (name "Net-(Q2-PadC)") (class "Default")
      (node (ref "Q2") (pin "C") (pinfunction "C_C") (pintype "passive"))
      (node (ref "Q3") (pin "B") (pinfunction "B_B") (pintype "passive"))
      (node (ref "R7") (pin "1") (pinfunction "1_1") (pintype "passive"))
    )
    (net (code "97") (name "VCC") (class "Default")
      (node (ref "C1") (pin "1") (pinfunction "1_1") (pintype "passive"))
      (node (ref "C10") (pin "1") (pinfunction "1_1") (pintype "passive"))
      (node (ref "C11") (pin "1") (pinfunction "1_1") (pintype "passive"))
      (node (ref "C12") (pin "1") (pinfunction "1_1") (pintype "passive"))
      (node (ref "C13") (pin "1") (pinfunction "1_1") (pintype "passive"))
      (node (ref "C14") (pin "1") (pinfunction "1_1") (pintype "passive"))
      (node (ref "C15") (pin "1") (pinfunction "1_1") (pintype "passive"))
      (node (ref "C16") (pin "1") (pinfunction "1_1") (pintype "passive"))
      (node (ref "C17") (pin "1") (pinfunction "1_1") (pintype "passive"))
      (node (ref "C18") (pin "1") (pinfunction "1_1") (pintype "passive"))
      (node (ref "C2") (pin "1") (pinfunction "1_1") (pintype "passive"))
      (node (ref "C20") (pin "1") (pinfunction "1_1") (pintype "passive"))
      (node (ref "C21") (pin "+") (pinfunction "+_+") (pintype "passive"))
      (node (ref "C23") (pin "1") (pinfunction "1_1") (pintype "passive"))
      (node (ref "C3") (pin "1") (pinfunction "1_1") (pintype "passive"))
      (node (ref "C4") (pin "1") (pinfunction "1_1") (pintype "passive"))
      (node (ref "C5") (pin "1") (pinfunction "1_1") (pintype "passive"))
      (node (ref "C6") (pin "1") (pinfunction "1_1") (pintype "passive"))
      (node (ref "C7") (pin "1") (pinfunction "1_1") (pintype "passive"))
      (node (ref "C8") (pin "1") (pinfunction "1_1") (pintype "passive"))
      (node (ref "C9") (pin "1") (pinfunction "1_1") (pintype "passive"))
      (node (ref "Q1") (pin "C") (pinfunction "C_C") (pintype "passive"))
      (node (ref "Q3") (pin "E") (pinfunction "E_E") (pintype "passive"))
      (node (ref "R2") (pin "2") (pinfunction "2_2") (pintype "passive"))
      (node (ref "R3") (pin "2") (pinfunction "2_2") (pintype "passive"))
      (node (ref "R7") (pin "2") (pinfunction "2_2") (pintype "passive"))
      (node (ref "R8") (pin "1") (pinfunction "1_1") (pintype "passive"))
      (node (ref "U$2") (pin "AA2") (pinfunction "1_AA2") (pintype "bidirectional"))
      (node (ref "U$2") (pin "BA2") (pinfunction "1_BA2") (pintype "bidirectional"))
    )
    (net (code "98") (name "unconnected-(E6B-~{Q}-Pad8)") (class "Default")
      (node (ref "E6") (pin "8") (pinfunction "~{Q}_8") (pintype "output"))
    )
    (net (code "99") (name "unconnected-(E16A-Q-Pad5)") (class "Default")
      (node (ref "E16") (pin "5") (pinfunction "Q_5") (pintype "output"))
    )
    (net (code "100") (name "unconnected-(E18A-O-Pad3)") (class "Default")
      (node (ref "E18") (pin "3") (pinfunction "O_3") (pintype "output"))
    )
    (net (code "101") (name "unconnected-(E18B-O-Pad6)") (class "Default")
      (node (ref "E18") (pin "6") (pinfunction "O_6") (pintype "output"))
    )
  )
)
